# PICV2.net
KiCad netlist of a schematic drawn in Altium Designer
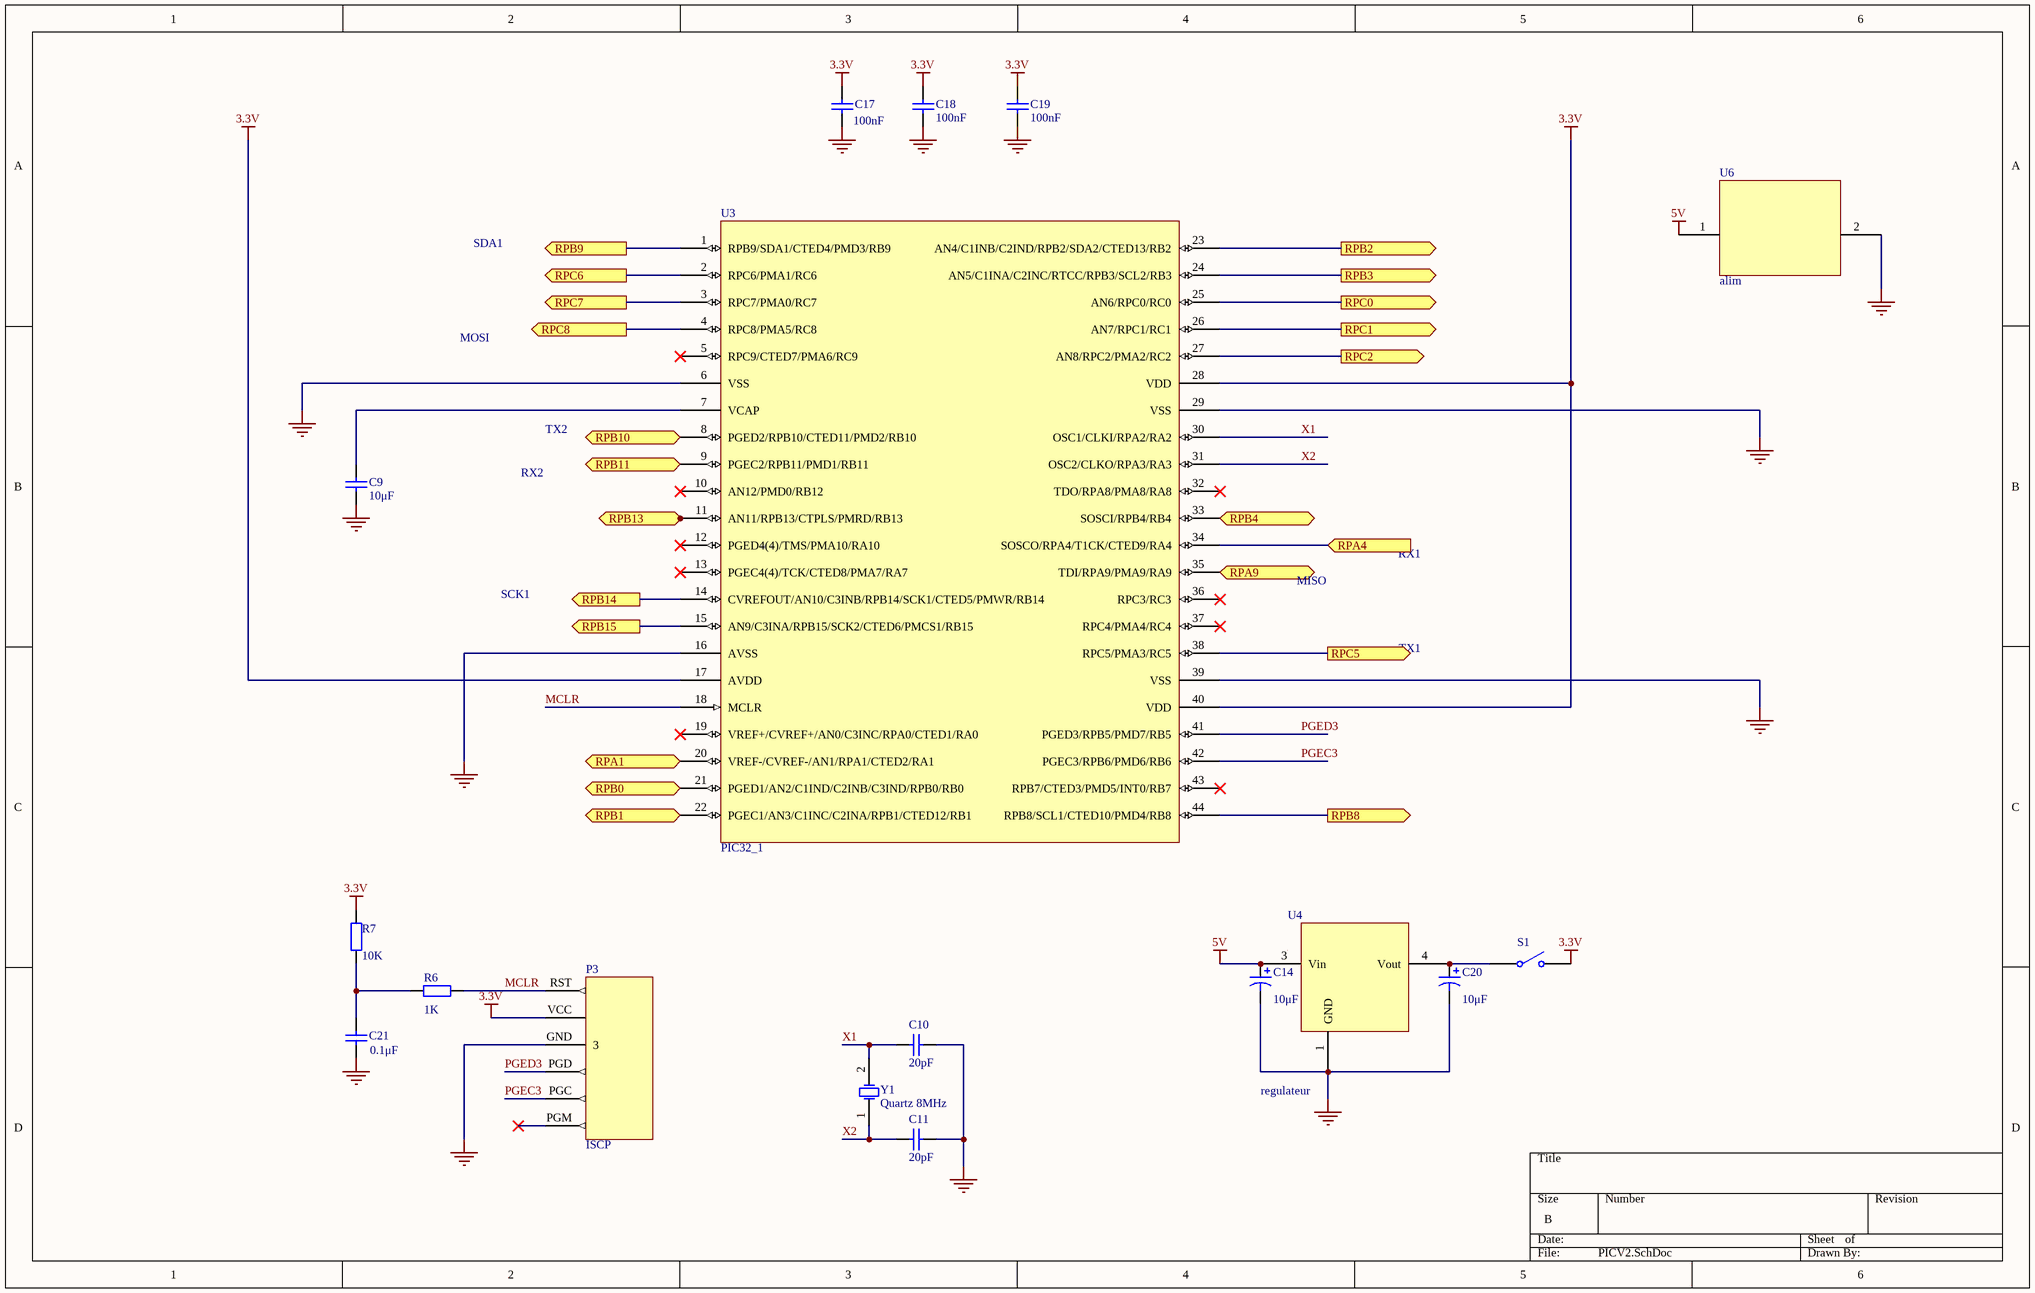
[diagram p0: PICV2.SchDoc]

(export (version "E")
  (design (tool "Eeschema 10.0.6"))
  (components
    (comp (ref "C9")
      (value "10μF")
      (footprint "0603")
      (description "Capacitor")
      (fields (field (name "Comment") "Cap") (field (name "PUBLISHER") "Altium Limited"))
      (libsource (lib "Miscellaneous Devices") (part "Cap"))
    )
    (comp (ref "C10")
      (value "20pF")
      (footprint "0603")
      (description "Capacitor")
      (fields (field (name "Comment") "Cap") (field (name "PUBLISHER") "Altium Limited"))
      (libsource (lib "Miscellaneous Devices") (part "Cap"))
    )
    (comp (ref "C11")
      (value "20pF")
      (footprint "0603")
      (description "Capacitor")
      (fields (field (name "Comment") "Cap") (field (name "PUBLISHER") "Altium Limited"))
      (libsource (lib "Miscellaneous Devices") (part "Cap"))
    )
    (comp (ref "C14")
      (value "10μF")
      (footprint "0603")
      (description "Polarized Capacitor (Radial)")
      (fields (field (name "Comment") "Cap Pol1") (field (name "PUBLISHER") "Altium Limited"))
      (libsource (lib "Miscellaneous Devices") (part "Cap Pol1"))
    )
    (comp (ref "C17")
      (value "100nF")
      (footprint "0603")
      (description "Capacitor")
      (fields (field (name "Comment") "Cap") (field (name "PUBLISHER") "Altium Limited"))
      (libsource (lib "Miscellaneous Devices") (part "Cap"))
    )
    (comp (ref "C18")
      (value "100nF")
      (footprint "0603")
      (description "Capacitor")
      (fields (field (name "Comment") "Cap") (field (name "PUBLISHER") "Altium Limited"))
      (libsource (lib "Miscellaneous Devices") (part "Cap"))
    )
    (comp (ref "C19")
      (value "100nF")
      (footprint "0603")
      (description "Capacitor")
      (fields (field (name "Comment") "Cap") (field (name "PUBLISHER") "Altium Limited"))
      (libsource (lib "Miscellaneous Devices") (part "Cap"))
    )
    (comp (ref "C20")
      (value "10μF")
      (footprint "0603")
      (description "Polarized Capacitor (Radial)")
      (fields (field (name "Comment") "Cap Pol1") (field (name "PUBLISHER") "Altium Limited"))
      (libsource (lib "Miscellaneous Devices") (part "Cap Pol1"))
    )
    (comp (ref "C21")
      (value "0.1μF")
      (footprint "0603")
      (description "Capacitor")
      (fields (field (name "Comment") "Cap") (field (name "PUBLISHER") "Altium Limited"))
      (libsource (lib "Miscellaneous Devices") (part "Cap"))
    )
    (comp (ref "P3") (value "ISCP") (footprint "ISCP") (libsource (lib "Schlib1") (part "ISCP")))
    (comp (ref "R6")
      (value "1K")
      (footprint "0603")
      (description "Resistor")
      (fields (field (name "Comment") "Res2") (field (name "PUBLISHER") "Altium Limited"))
      (libsource (lib "") (part "Res2_1"))
    )
    (comp (ref "R7")
      (value "10K")
      (footprint "0603")
      (description "Resistor")
      (fields (field (name "Comment") "Res2") (field (name "PUBLISHER") "Altium Limited"))
      (libsource (lib "Miscellaneous Devices") (part "Res2"))
    )
    (comp (ref "S1")
      (value "SW-SPST")
      (footprint "SPST-2")
      (description "Single-Pole, Single-Throw Switch")
      (fields (field (name "PUBLISHER") "Altium Limited"))
      (libsource (lib "Miscellaneous Devices") (part "SW-SPST"))
    )
    (comp (ref "U3") (value "PIC32_1") (footprint "PIC32") (libsource (lib "Schlib1") (part "PIC32_1")))
    (comp (ref "U4")
      (value "regulateur")
      (footprint "regulateur")
      (libsource (lib "Schlib1") (part "regulateur"))
    )
    (comp (ref "U6") (value "alim") (footprint "Alim") (libsource (lib "Schlib1") (part "alim")))
    (comp (ref "Y1")
      (value "Quartz 8MHz")
      (footprint "quartz")
      (description "Crystal Oscillator")
      (fields (field (name "PUBLISHER") "Altium Limited"))
      (libsource (lib "Miscellaneous Devices") (part "XTAL"))
    )
  )
  (nets
    (net (code "1") (name "/MCLR") (class "Default")
      (node (ref "P3") (pin "RST") (pinfunction "1_RST") (pintype "output"))
      (node (ref "R6") (pin "2") (pinfunction "2_2") (pintype "passive"))
      (node (ref "U3") (pin "18") (pinfunction "MCLR_18") (pintype "input"))
    )
    (net (code "2") (name "/PGEC3") (class "Default")
      (node (ref "P3") (pin "PGC") (pinfunction "5_PGC") (pintype "output"))
      (node (ref "U3") (pin "42") (pinfunction "PGEC3/RPB6/PMD6/RB6_42") (pintype "bidirectional"))
    )
    (net (code "3") (name "/PGED3") (class "Default")
      (node (ref "P3") (pin "PGD") (pinfunction "4_PGD") (pintype "output"))
      (node (ref "U3") (pin "41") (pinfunction "PGED3/RPB5/PMD7/RB5_41") (pintype "bidirectional"))
    )
    (net (code "4") (name "/RPA1") (class "Default")
      (node (ref "U3") (pin "20") (pinfunction "VREF-/CVREF-/AN1/RPA1/CTED2/RA1_20") (pintype "bidirectional"))
    )
    (net (code "5") (name "/RPA4") (class "Default")
      (node (ref "U3") (pin "34") (pinfunction "SOSCO/RPA4/T1CK/CTED9/RA4_34") (pintype "bidirectional"))
    )
    (net (code "6") (name "/RPA9") (class "Default")
      (node (ref "U3") (pin "35") (pinfunction "TDI/RPA9/PMA9/RA9_35") (pintype "bidirectional"))
    )
    (net (code "7") (name "/RPB0") (class "Default")
      (node (ref "U3") (pin "21") (pinfunction "PGED1/AN2/C1IND/C2INB/C3IND/RPB0/RB0_21") (pintype "bidirectional"))
    )
    (net (code "8") (name "/RPB1") (class "Default")
      (node (ref "U3") (pin "22") (pinfunction "PGEC1/AN3/C1INC/C2INA/RPB1/CTED12/RB1_22") (pintype "bidirectional"))
    )
    (net (code "9") (name "/RPB2") (class "Default")
      (node (ref "U3") (pin "23") (pinfunction "AN4/C1INB/C2IND/RPB2/SDA2/CTED13/RB2_23") (pintype "bidirectional"))
    )
    (net (code "10") (name "/RPB3") (class "Default")
      (node (ref "U3") (pin "24") (pinfunction "AN5/C1INA/C2INC/RTCC/RPB3/SCL2/RB3_24") (pintype "bidirectional"))
    )
    (net (code "11") (name "/RPB4") (class "Default")
      (node (ref "U3") (pin "33") (pinfunction "SOSCI/RPB4/RB4_33") (pintype "bidirectional"))
    )
    (net (code "12") (name "/RPB8") (class "Default")
      (node (ref "U3") (pin "44") (pinfunction "RPB8/SCL1/CTED10/PMD4/RB8_44") (pintype "bidirectional"))
    )
    (net (code "13") (name "/RPB9") (class "Default")
      (node (ref "U3") (pin "1") (pinfunction "RPB9/SDA1/CTED4/PMD3/RB9_1") (pintype "bidirectional"))
    )
    (net (code "14") (name "/RPB10") (class "Default")
      (node (ref "U3") (pin "8") (pinfunction "PGED2/RPB10/CTED11/PMD2/RB10_8") (pintype "bidirectional"))
    )
    (net (code "15") (name "/RPB11") (class "Default")
      (node (ref "U3") (pin "9") (pinfunction "PGEC2/RPB11/PMD1/RB11_9") (pintype "bidirectional"))
    )
    (net (code "17") (name "/RPB14") (class "Default")
      (node (ref "U3") (pin "14") (pinfunction "CVREFOUT/AN10/C3INB/RPB14/SCK1/CTED5/PMWR/RB14_14") (pintype "bidirectional"))
    )
    (net (code "18") (name "/RPB15") (class "Default")
      (node (ref "U3") (pin "15") (pinfunction "AN9/C3INA/RPB15/SCK2/CTED6/PMCS1/RB15_15") (pintype "bidirectional"))
    )
    (net (code "19") (name "/RPC0") (class "Default")
      (node (ref "U3") (pin "25") (pinfunction "AN6/RPC0/RC0_25") (pintype "bidirectional"))
    )
    (net (code "20") (name "/RPC1") (class "Default")
      (node (ref "U3") (pin "26") (pinfunction "AN7/RPC1/RC1_26") (pintype "bidirectional"))
    )
    (net (code "21") (name "/RPC2") (class "Default")
      (node (ref "U3") (pin "27") (pinfunction "AN8/RPC2/PMA2/RC2_27") (pintype "bidirectional"))
    )
    (net (code "22") (name "/RPC5") (class "Default")
      (node (ref "U3") (pin "38") (pinfunction "RPC5/PMA3/RC5_38") (pintype "bidirectional"))
    )
    (net (code "23") (name "/RPC6") (class "Default")
      (node (ref "U3") (pin "2") (pinfunction "RPC6/PMA1/RC6_2") (pintype "bidirectional"))
    )
    (net (code "24") (name "/RPC7") (class "Default")
      (node (ref "U3") (pin "3") (pinfunction "RPC7/PMA0/RC7_3") (pintype "bidirectional"))
    )
    (net (code "25") (name "/RPC8") (class "Default")
      (node (ref "U3") (pin "4") (pinfunction "RPC8/PMA5/RC8_4") (pintype "bidirectional"))
    )
    (net (code "26") (name "/X1") (class "Default")
      (node (ref "C10") (pin "2") (pinfunction "2_2") (pintype "passive"))
      (node (ref "U3") (pin "30") (pinfunction "OSC1/CLKI/RPA2/RA2_30") (pintype "bidirectional"))
      (node (ref "Y1") (pin "2") (pinfunction "OSC2_2") (pintype "passive"))
    )
    (net (code "27") (name "/X2") (class "Default")
      (node (ref "C11") (pin "2") (pinfunction "2_2") (pintype "passive"))
      (node (ref "U3") (pin "31") (pinfunction "OSC2/CLKO/RPA3/RA3_31") (pintype "bidirectional"))
      (node (ref "Y1") (pin "1") (pinfunction "OSC1_1") (pintype "passive"))
    )
    (net (code "28") (name "3.3V") (class "Default")
      (node (ref "C17") (pin "2") (pinfunction "2_2") (pintype "passive"))
      (node (ref "C18") (pin "1") (pinfunction "1_1") (pintype "passive"))
      (node (ref "C19") (pin "1") (pinfunction "1_1") (pintype "passive"))
      (node (ref "P3") (pin "VCC") (pinfunction "2_VCC") (pintype "passive"))
      (node (ref "R7") (pin "2") (pinfunction "2_2") (pintype "passive"))
      (node (ref "S1") (pin "2") (pinfunction "NO_2") (pintype "passive"))
      (node (ref "U3") (pin "17") (pinfunction "AVDD_17") (pintype "passive"))
      (node (ref "U3") (pin "28") (pinfunction "VDD_28") (pintype "passive"))
      (node (ref "U3") (pin "40") (pinfunction "VDD_40") (pintype "passive"))
    )
    (net (code "29") (name "5V") (class "Default")
      (node (ref "C14") (pin "1") (pinfunction "1_1") (pintype "passive"))
      (node (ref "U4") (pin "3") (pinfunction "Vin_3") (pintype "power_in"))
      (node (ref "U6") (pin "1") (pinfunction "1_1") (pintype "passive"))
    )
    (net (code "30") (name "GND") (class "Default")
      (node (ref "C10") (pin "1") (pinfunction "1_1") (pintype "passive"))
      (node (ref "C11") (pin "1") (pinfunction "1_1") (pintype "passive"))
      (node (ref "C14") (pin "2") (pinfunction "2_2") (pintype "passive"))
      (node (ref "C17") (pin "1") (pinfunction "1_1") (pintype "passive"))
      (node (ref "C18") (pin "2") (pinfunction "2_2") (pintype "passive"))
      (node (ref "C19") (pin "2") (pinfunction "2_2") (pintype "passive"))
      (node (ref "C20") (pin "2") (pinfunction "2_2") (pintype "passive"))
      (node (ref "C21") (pin "1") (pinfunction "1_1") (pintype "passive"))
      (node (ref "C9") (pin "2") (pinfunction "2_2") (pintype "passive"))
      (node (ref "P3") (pin "GND") (pinfunction "3_GND") (pintype "passive"))
      (node (ref "U3") (pin "16") (pinfunction "AVSS_16") (pintype "passive"))
      (node (ref "U3") (pin "29") (pinfunction "VSS_29") (pintype "power_in"))
      (node (ref "U3") (pin "39") (pinfunction "VSS_39") (pintype "power_in"))
      (node (ref "U3") (pin "6") (pinfunction "VSS_6") (pintype "passive"))
      (node (ref "U4") (pin "1") (pinfunction "GND_1") (pintype "passive"))
      (node (ref "U6") (pin "2") (pinfunction "2_2") (pintype "passive"))
    )
    (net (code "31") (name "Net-(C21-Pad2)") (class "Default")
      (node (ref "C21") (pin "2") (pinfunction "2_2") (pintype "passive"))
      (node (ref "R6") (pin "1") (pinfunction "1_1") (pintype "passive"))
      (node (ref "R7") (pin "1") (pinfunction "1_1") (pintype "passive"))
    )
    (net (code "32") (name "Net-(S1-COMMON)") (class "Default")
      (node (ref "C20") (pin "1") (pinfunction "1_1") (pintype "passive"))
      (node (ref "S1") (pin "1") (pinfunction "COMMON_1") (pintype "passive"))
      (node (ref "U4") (pin "4") (pinfunction "Vout_4") (pintype "passive"))
    )
    (net (code "33") (name "Net-(U3-VCAP)") (class "Default")
      (node (ref "C9") (pin "1") (pinfunction "1_1") (pintype "passive"))
      (node (ref "U3") (pin "7") (pinfunction "VCAP_7") (pintype "passive"))
    )
    (net (code "34") (name "unconnected-(P3-6-PadPGM)") (class "Default")
      (node (ref "P3") (pin "PGM") (pinfunction "6_PGM") (pintype "output+no_connect"))
    )
    (net (code "35") (name "unconnected-(U3-AN11{slash}RPB13{slash}CTPLS{slash}PMRD{slash}RB13-Pad11)") (class "Default")
      (node (ref "U3") (pin "11") (pinfunction "AN11/RPB13/CTPLS/PMRD/RB13_11") (pintype "bidirectional"))
    )
    (net (code "36") (name "unconnected-(U3-AN12{slash}PMD0{slash}RB12-Pad10)") (class "Default")
      (node (ref "U3") (pin "10") (pinfunction "AN12/PMD0/RB12_10") (pintype "bidirectional+no_connect"))
    )
    (net (code "37") (name "unconnected-(U3-PGEC4(4){slash}TCK{slash}CTED8{slash}PMA7{slash}RA7-Pad13)") (class "Default")
      (node (ref "U3") (pin "13") (pinfunction "PGEC4(4)/TCK/CTED8/PMA7/RA7_13") (pintype "bidirectional+no_connect"))
    )
    (net (code "38") (name "unconnected-(U3-PGED4(4){slash}TMS{slash}PMA10{slash}RA10-Pad12)") (class "Default")
      (node (ref "U3") (pin "12") (pinfunction "PGED4(4)/TMS/PMA10/RA10_12") (pintype "bidirectional+no_connect"))
    )
    (net (code "39") (name "unconnected-(U3-RPB7{slash}CTED3{slash}PMD5{slash}INT0{slash}RB7-Pad43)") (class "Default")
      (node (ref "U3") (pin "43") (pinfunction "RPB7/CTED3/PMD5/INT0/RB7_43") (pintype "bidirectional+no_connect"))
    )
    (net (code "40") (name "unconnected-(U3-RPC3{slash}RC3-Pad36)") (class "Default")
      (node (ref "U3") (pin "36") (pinfunction "RPC3/RC3_36") (pintype "bidirectional+no_connect"))
    )
    (net (code "41") (name "unconnected-(U3-RPC4{slash}PMA4{slash}RC4-Pad37)") (class "Default")
      (node (ref "U3") (pin "37") (pinfunction "RPC4/PMA4/RC4_37") (pintype "bidirectional+no_connect"))
    )
    (net (code "42") (name "unconnected-(U3-RPC9{slash}CTED7{slash}PMA6{slash}RC9-Pad5)") (class "Default")
      (node (ref "U3") (pin "5") (pinfunction "RPC9/CTED7/PMA6/RC9_5") (pintype "bidirectional+no_connect"))
    )
    (net (code "43") (name "unconnected-(U3-TDO{slash}RPA8{slash}PMA8{slash}RA8-Pad32)") (class "Default")
      (node (ref "U3") (pin "32") (pinfunction "TDO/RPA8/PMA8/RA8_32") (pintype "bidirectional+no_connect"))
    )
    (net (code "44") (name "unconnected-(U3-VREF+{slash}CVREF+{slash}AN0{slash}C3INC{slash}RPA0{slash}CTED1{slash}RA0-Pad19)") (class "Default")
      (node (ref "U3") (pin "19") (pinfunction "VREF+/CVREF+/AN0/C3INC/RPA0/CTED1/RA0_19") (pintype "bidirectional+no_connect"))
    )
  )
)
